# Ethernet_Shield_v2_0.net
KiCad netlist of a schematic drawn in EAGLE
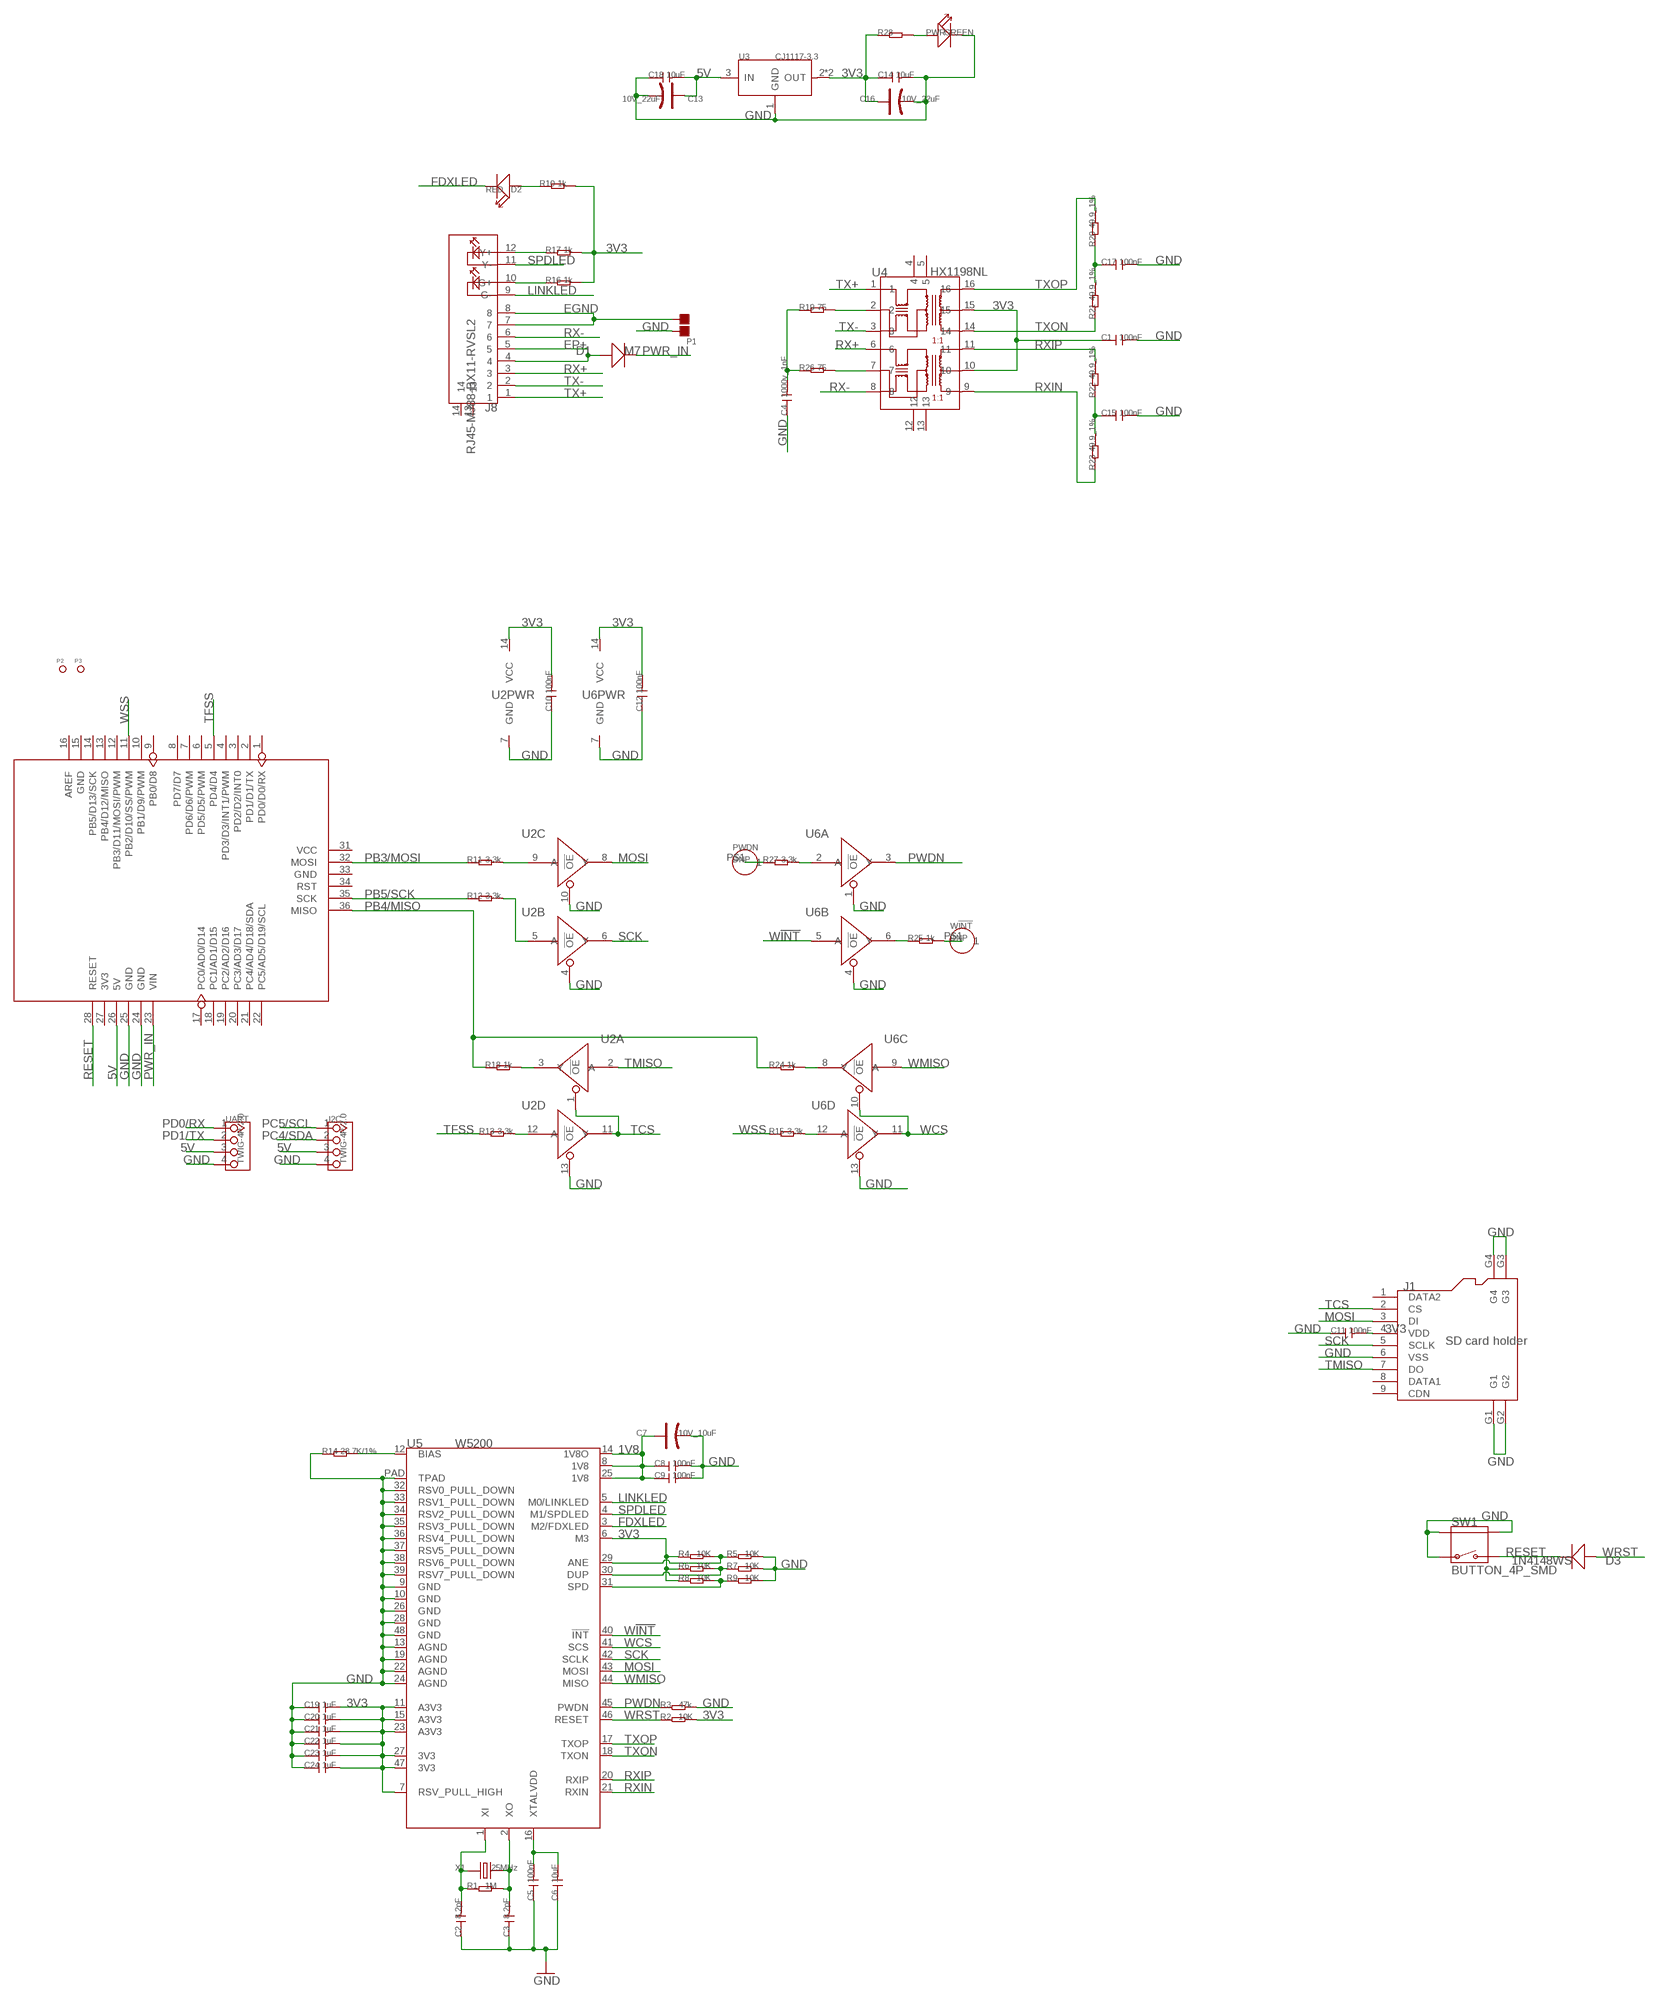
[diagram p0: schematic, sheet 1]

(export (version "E")
  (design (tool "Eeschema 10.0.6"))
  (components
    (comp (ref "C1")
      (value "100nF")
      (footprint "eagle-import:C0603")
      (libsource (lib "eagle-import") (part "C-0603"))
    )
    (comp (ref "C2")
      (value "8.2pF")
      (footprint "eagle-import:C0603")
      (libsource (lib "eagle-import") (part "C-0603"))
    )
    (comp (ref "C3")
      (value "8.2pF")
      (footprint "eagle-import:C0603")
      (libsource (lib "eagle-import") (part "C-0603"))
    )
    (comp (ref "C4")
      (value "1000v_1nF")
      (footprint "eagle-import:C1206")
      (libsource (lib "eagle-import") (part "C-1206"))
    )
    (comp (ref "C5")
      (value "100nF")
      (footprint "eagle-import:C0603")
      (libsource (lib "eagle-import") (part "C-0603"))
    )
    (comp (ref "C6")
      (value "10uF")
      (footprint "eagle-import:C0805")
      (libsource (lib "eagle-import") (part "C-0805"))
    )
    (comp (ref "C7")
      (value "10V_10uF")
      (footprint "eagle-import:AVX-A")
      (libsource (lib "eagle-import") (part "CAP-AVX-A"))
    )
    (comp (ref "C8")
      (value "100nF")
      (footprint "eagle-import:C0603")
      (libsource (lib "eagle-import") (part "C-0603"))
    )
    (comp (ref "C9")
      (value "100nF")
      (footprint "eagle-import:C0603")
      (libsource (lib "eagle-import") (part "C-0603"))
    )
    (comp (ref "C10")
      (value "100nF")
      (footprint "eagle-import:C0603")
      (libsource (lib "eagle-import") (part "C-0603"))
    )
    (comp (ref "C11")
      (value "100nF")
      (footprint "eagle-import:C0603")
      (libsource (lib "eagle-import") (part "C-0603"))
    )
    (comp (ref "C12")
      (value "100nF")
      (footprint "eagle-import:C0603")
      (libsource (lib "eagle-import") (part "C-0603"))
    )
    (comp (ref "C13")
      (value "10V_22uF")
      (footprint "eagle-import:AVX-B")
      (libsource (lib "eagle-import") (part "CAP-AVX-B"))
    )
    (comp (ref "C14")
      (value "10uF")
      (footprint "eagle-import:C0805")
      (libsource (lib "eagle-import") (part "C-0805"))
    )
    (comp (ref "C15")
      (value "100nF")
      (footprint "eagle-import:C0603")
      (libsource (lib "eagle-import") (part "C-0603"))
    )
    (comp (ref "C16")
      (value "10V_22uF")
      (footprint "eagle-import:AVX-B")
      (libsource (lib "eagle-import") (part "CAP-AVX-B"))
    )
    (comp (ref "C17")
      (value "100nF")
      (footprint "eagle-import:C0603")
      (libsource (lib "eagle-import") (part "C-0603"))
    )
    (comp (ref "C18")
      (value "10uF")
      (footprint "eagle-import:C0805")
      (libsource (lib "eagle-import") (part "C-0805"))
    )
    (comp (ref "C19")
      (value "1uF")
      (footprint "eagle-import:C0805")
      (libsource (lib "eagle-import") (part "C-0805"))
    )
    (comp (ref "C20")
      (value "1uF")
      (footprint "eagle-import:C0805")
      (libsource (lib "eagle-import") (part "C-0805"))
    )
    (comp (ref "C21")
      (value "1uF")
      (footprint "eagle-import:C0805")
      (libsource (lib "eagle-import") (part "C-0805"))
    )
    (comp (ref "C22")
      (value "1uF")
      (footprint "eagle-import:C0805")
      (libsource (lib "eagle-import") (part "C-0805"))
    )
    (comp (ref "C23")
      (value "1uF")
      (footprint "eagle-import:C0805")
      (libsource (lib "eagle-import") (part "C-0805"))
    )
    (comp (ref "C24")
      (value "1uF")
      (footprint "eagle-import:C0805")
      (libsource (lib "eagle-import") (part "C-0805"))
    )
    (comp (ref "D1")
      (value "M7")
      (footprint "eagle-import:D2010")
      (libsource (lib "eagle-import") (part "D'SMA'"))
    )
    (comp (ref "D2")
      (value "RED")
      (footprint "eagle-import:LED-0603")
      (libsource (lib "eagle-import") (part "LED'0603'"))
    )
    (comp (ref "D3")
      (value "1N4148WS")
      (footprint "eagle-import:SOD323")
      (libsource (lib "eagle-import") (part "D'0805'"))
    )
    (comp (ref "I2C")
      (value "TWIG-4P-2.0")
      (footprint "eagle-import:4P-2.0")
      (libsource (lib "eagle-import") (part "TWIG-4P-2.0-2.0"))
    )
    (comp (ref "J1")
      (value "SD card holder")
      (footprint "eagle-import:9P-SMD-W_-RING")
      (libsource (lib "eagle-import") (part "HOLDER-MICROSD-9P"))
    )
    (comp (ref "J8")
      (value "RJ45-MJ88-BX11-RVSL2")
      (footprint "eagle-import:RJ45-MJ88-BX11-RVSL2")
      (libsource (lib "eagle-import") (part "RJ45-MJ88-BX11-RVSL2"))
    )
    (comp (ref "P1")
      (value "DNP")
      (footprint "eagle-import:2P-SMD-1.78X1.27")
      (libsource (lib "eagle-import") (part "PAD-JUMPER-2P"))
    )
    (comp (ref "P2")
      (value "PAD-MARK")
      (footprint "eagle-import:ROUND-MARK-1.0")
      (fields (field (name "PARTNO") "DNP"))
      (libsource (lib "eagle-import") (part "PAD-MARK"))
    )
    (comp (ref "P3")
      (value "PAD-MARK")
      (footprint "eagle-import:ROUND-MARK-1.0")
      (fields (field (name "PARTNO") "DNP"))
      (libsource (lib "eagle-import") (part "PAD-MARK"))
    )
    (comp (ref "PWDN")
      (value "DNP")
      (footprint "eagle-import:1P-65_35MIL")
      (libsource (lib "eagle-import") (part "HEADER-1P-35"))
    )
    (comp (ref "PWR")
      (value "GREEN")
      (footprint "eagle-import:LED-0603")
      (libsource (lib "eagle-import") (part "LED'0603'"))
    )
    (comp (ref "R1")
      (value "1M")
      (footprint "eagle-import:R0603")
      (libsource (lib "eagle-import") (part "R-0603"))
    )
    (comp (ref "R2")
      (value "10K")
      (footprint "eagle-import:R0603")
      (libsource (lib "eagle-import") (part "R-0603"))
    )
    (comp (ref "R3")
      (value "47k")
      (footprint "eagle-import:R0603")
      (libsource (lib "eagle-import") (part "R-0603"))
    )
    (comp (ref "R4")
      (value "10K")
      (footprint "eagle-import:R0603")
      (libsource (lib "eagle-import") (part "R-0603"))
    )
    (comp (ref "R5")
      (value "10K")
      (footprint "eagle-import:R0603")
      (libsource (lib "eagle-import") (part "R-0603"))
    )
    (comp (ref "R6")
      (value "10K")
      (footprint "eagle-import:R0603")
      (libsource (lib "eagle-import") (part "R-0603"))
    )
    (comp (ref "R7")
      (value "10K")
      (footprint "eagle-import:R0603")
      (libsource (lib "eagle-import") (part "R-0603"))
    )
    (comp (ref "R8")
      (value "10K")
      (footprint "eagle-import:R0603")
      (libsource (lib "eagle-import") (part "R-0603"))
    )
    (comp (ref "R9")
      (value "10K")
      (footprint "eagle-import:R0603")
      (libsource (lib "eagle-import") (part "R-0603"))
    )
    (comp (ref "R10")
      (value "1k")
      (footprint "eagle-import:R0603")
      (libsource (lib "eagle-import") (part "R-0603"))
    )
    (comp (ref "R11")
      (value "3.3k")
      (footprint "eagle-import:R0603")
      (libsource (lib "eagle-import") (part "R-0603"))
    )
    (comp (ref "R12")
      (value "3.3k")
      (footprint "eagle-import:R0603")
      (libsource (lib "eagle-import") (part "R-0603"))
    )
    (comp (ref "R13")
      (value "3.3k")
      (footprint "eagle-import:R0603")
      (libsource (lib "eagle-import") (part "R-0603"))
    )
    (comp (ref "R14")
      (value "28.7K/1%")
      (footprint "eagle-import:R0603")
      (libsource (lib "eagle-import") (part "R-0603"))
    )
    (comp (ref "R15")
      (value "3.3k")
      (footprint "eagle-import:R0603")
      (libsource (lib "eagle-import") (part "R-0603"))
    )
    (comp (ref "R16")
      (value "1k")
      (footprint "eagle-import:R0603")
      (libsource (lib "eagle-import") (part "R-0603"))
    )
    (comp (ref "R17")
      (value "1k")
      (footprint "eagle-import:R0603")
      (libsource (lib "eagle-import") (part "R-0603"))
    )
    (comp (ref "R18")
      (value "1k")
      (footprint "eagle-import:R0603")
      (libsource (lib "eagle-import") (part "R-0603"))
    )
    (comp (ref "R19")
      (value "75")
      (footprint "eagle-import:R0603")
      (libsource (lib "eagle-import") (part "R-0603"))
    )
    (comp (ref "R20")
      (value "49.9_1%")
      (footprint "eagle-import:R0603")
      (libsource (lib "eagle-import") (part "R-0603"))
    )
    (comp (ref "R21")
      (value "49.9_1%")
      (footprint "eagle-import:R0603")
      (libsource (lib "eagle-import") (part "R-0603"))
    )
    (comp (ref "R22")
      (value "49.9_1%")
      (footprint "eagle-import:R0603")
      (libsource (lib "eagle-import") (part "R-0603"))
    )
    (comp (ref "R23")
      (value "49.9_1%")
      (footprint "eagle-import:R0603")
      (libsource (lib "eagle-import") (part "R-0603"))
    )
    (comp (ref "R24")
      (value "1k")
      (footprint "eagle-import:R0603")
      (libsource (lib "eagle-import") (part "R-0603"))
    )
    (comp (ref "R25")
      (value "1k")
      (footprint "eagle-import:R0603")
      (libsource (lib "eagle-import") (part "R-0603"))
    )
    (comp (ref "R26")
      (value "75")
      (footprint "eagle-import:R0603")
      (libsource (lib "eagle-import") (part "R-0603"))
    )
    (comp (ref "R27")
      (value "3.3k")
      (footprint "eagle-import:R0603")
      (libsource (lib "eagle-import") (part "R-0603"))
    )
    (comp (ref "R28")
      (value "R-0603")
      (footprint "eagle-import:R0603")
      (libsource (lib "eagle-import") (part "R-0603"))
    )
    (comp (ref "SW1")
      (value "BUTTON_4P_SMD")
      (footprint "eagle-import:4P-SMD-7X3.5X3.5")
      (libsource (lib "eagle-import") (part "BUTTON_4P_SMD"))
    )
    (comp (ref "U1")
      (value "ARDUINO")
      (footprint "eagle-import:ARDUINO")
      (libsource (lib "eagle-import") (part "ARDUINO"))
    )
    (comp (ref "U2")
      (value "74VHC125PW")
      (footprint "eagle-import:TSSOP14")
      (libsource (lib "eagle-import") (part "74V125PWHC"))
    )
    (comp (ref "U3")
      (value "CJ1117-3.3")
      (footprint "eagle-import:SOT-223")
      (libsource (lib "eagle-import") (part "LD1117S"))
    )
    (comp (ref "U4")
      (value "HX1198NL")
      (footprint "eagle-import:SOIC16-9.53")
      (libsource (lib "eagle-import") (part "HX1198NL"))
    )
    (comp (ref "U5")
      (value "W5200")
      (footprint "eagle-import:QFN48")
      (libsource (lib "eagle-import") (part "W5200"))
    )
    (comp (ref "U6")
      (value "74VHC125PW")
      (footprint "eagle-import:TSSOP14")
      (libsource (lib "eagle-import") (part "74V125PWHC"))
    )
    (comp (ref "UART")
      (value "TWIG-4P-2.0")
      (footprint "eagle-import:4P-2.0")
      (libsource (lib "eagle-import") (part "TWIG-4P-2.0-2.0"))
    )
    (comp (ref "W!INT")
      (value "DNP")
      (footprint "eagle-import:1P-65_35MIL")
      (libsource (lib "eagle-import") (part "HEADER-1P-35"))
    )
    (comp (ref "X1")
      (value "25MHz")
      (footprint "eagle-import:2P-SMD-5X3.2")
      (libsource (lib "eagle-import") (part "CRYSTAL'5032'"))
    )
  )
  (nets
    (net (code "1") (name "/1V8") (class "Default")
      (node (ref "C7") (pin "+") (pinfunction "+_+") (pintype "passive"))
      (node (ref "C8") (pin "1") (pinfunction "1_1") (pintype "passive"))
      (node (ref "C9") (pin "1") (pinfunction "1_1") (pintype "passive"))
      (node (ref "U5") (pin "14") (pinfunction "1V8O_14") (pintype "bidirectional"))
      (node (ref "U5") (pin "25") (pinfunction "1V8_25") (pintype "bidirectional"))
      (node (ref "U5") (pin "8") (pinfunction "1V8_8") (pintype "bidirectional"))
    )
    (net (code "2") (name "/3V3") (class "Default")
      (node (ref "C1") (pin "1") (pinfunction "1_1") (pintype "passive"))
      (node (ref "C10") (pin "2") (pinfunction "2_2") (pintype "passive"))
      (node (ref "C11") (pin "2") (pinfunction "2_2") (pintype "passive"))
      (node (ref "C12") (pin "2") (pinfunction "2_2") (pintype "passive"))
      (node (ref "C14") (pin "1") (pinfunction "1_1") (pintype "passive"))
      (node (ref "C16") (pin "+") (pinfunction "+_+") (pintype "passive"))
      (node (ref "C19") (pin "2") (pinfunction "2_2") (pintype "passive"))
      (node (ref "C20") (pin "2") (pinfunction "2_2") (pintype "passive"))
      (node (ref "C21") (pin "2") (pinfunction "2_2") (pintype "passive"))
      (node (ref "C22") (pin "2") (pinfunction "2_2") (pintype "passive"))
      (node (ref "C23") (pin "2") (pinfunction "2_2") (pintype "passive"))
      (node (ref "C24") (pin "2") (pinfunction "2_2") (pintype "passive"))
      (node (ref "J1") (pin "4") (pinfunction "VDD_4") (pintype "bidirectional"))
      (node (ref "R10") (pin "2") (pinfunction "2_2") (pintype "passive"))
      (node (ref "R16") (pin "2") (pinfunction "2_2") (pintype "passive"))
      (node (ref "R17") (pin "2") (pinfunction "2_2") (pintype "passive"))
      (node (ref "R2") (pin "2") (pinfunction "2_2") (pintype "passive"))
      (node (ref "R28") (pin "1") (pinfunction "1_1") (pintype "passive"))
      (node (ref "R4") (pin "1") (pinfunction "1_1") (pintype "passive"))
      (node (ref "R6") (pin "1") (pinfunction "1_1") (pintype "passive"))
      (node (ref "R8") (pin "1") (pinfunction "1_1") (pintype "passive"))
      (node (ref "U2") (pin "14") (pinfunction "VCC_14") (pintype "power_in"))
      (node (ref "U3") (pin "2") (pinfunction "OUT_2") (pintype "bidirectional"))
      (node (ref "U3") (pin "TER") (pinfunction "OUT_TER") (pintype "bidirectional"))
      (node (ref "U4") (pin "10") (pinfunction "10_10") (pintype "bidirectional"))
      (node (ref "U4") (pin "15") (pinfunction "15_15") (pintype "bidirectional"))
      (node (ref "U5") (pin "11") (pinfunction "A3V3_11") (pintype "bidirectional"))
      (node (ref "U5") (pin "15") (pinfunction "A3V3_15") (pintype "bidirectional"))
      (node (ref "U5") (pin "23") (pinfunction "A3V3_23") (pintype "bidirectional"))
      (node (ref "U5") (pin "27") (pinfunction "3V3_27") (pintype "bidirectional"))
      (node (ref "U5") (pin "47") (pinfunction "3V3_47") (pintype "bidirectional"))
      (node (ref "U5") (pin "6") (pinfunction "M3_6") (pintype "bidirectional"))
      (node (ref "U5") (pin "7") (pinfunction "RSV_PULL_HIGH_7") (pintype "bidirectional"))
      (node (ref "U6") (pin "14") (pinfunction "VCC_14") (pintype "power_in"))
    )
    (net (code "3") (name "/5V") (class "Default")
      (node (ref "C13") (pin "+") (pinfunction "+_+") (pintype "passive"))
      (node (ref "C18") (pin "2") (pinfunction "2_2") (pintype "passive"))
      (node (ref "I2C") (pin "3") (pinfunction "3_3") (pintype "bidirectional"))
      (node (ref "U1") (pin "26") (pinfunction "5V_26") (pintype "bidirectional"))
      (node (ref "U3") (pin "3") (pinfunction "IN_3") (pintype "bidirectional"))
      (node (ref "UART") (pin "3") (pinfunction "3_3") (pintype "bidirectional"))
    )
    (net (code "4") (name "/EGND") (class "Default")
      (node (ref "J8") (pin "7") (pinfunction "7_7") (pintype "bidirectional"))
      (node (ref "J8") (pin "8") (pinfunction "8_8") (pintype "bidirectional"))
      (node (ref "P1") (pin "1") (pinfunction "1_1") (pintype "bidirectional"))
    )
    (net (code "5") (name "/EP+") (class "Default")
      (node (ref "D1") (pin "+") (pinfunction "+_+") (pintype "passive"))
      (node (ref "J8") (pin "4") (pinfunction "4_4") (pintype "bidirectional"))
      (node (ref "J8") (pin "5") (pinfunction "5_5") (pintype "bidirectional"))
    )
    (net (code "6") (name "/FDXLED") (class "Default")
      (node (ref "D2") (pin "-") (pinfunction "-_-") (pintype "passive"))
      (node (ref "U5") (pin "3") (pinfunction "M2/FDXLED_3") (pintype "bidirectional"))
    )
    (net (code "7") (name "/LINKLED") (class "Default")
      (node (ref "J8") (pin "9") (pinfunction "G-_9") (pintype "bidirectional"))
      (node (ref "U5") (pin "5") (pinfunction "M0/LINKLED_5") (pintype "bidirectional"))
    )
    (net (code "8") (name "/MOSI") (class "Default")
      (node (ref "J1") (pin "3") (pinfunction "DI_3") (pintype "bidirectional"))
      (node (ref "U2") (pin "8") (pinfunction "Y_8") (pintype "bidirectional"))
      (node (ref "U5") (pin "43") (pinfunction "MOSI_43") (pintype "bidirectional"))
    )
    (net (code "9") (name "/PB3{slash}MOSI") (class "Default")
      (node (ref "R11") (pin "1") (pinfunction "1_1") (pintype "passive"))
      (node (ref "U1") (pin "32") (pinfunction "MOSI_32") (pintype "bidirectional"))
    )
    (net (code "10") (name "/PB4{slash}MISO") (class "Default")
      (node (ref "R18") (pin "1") (pinfunction "1_1") (pintype "passive"))
      (node (ref "R24") (pin "1") (pinfunction "1_1") (pintype "passive"))
      (node (ref "U1") (pin "36") (pinfunction "MISO_36") (pintype "bidirectional"))
    )
    (net (code "11") (name "/PB5{slash}SCK") (class "Default")
      (node (ref "R12") (pin "1") (pinfunction "1_1") (pintype "passive"))
      (node (ref "U1") (pin "35") (pinfunction "SCK_35") (pintype "bidirectional"))
    )
    (net (code "12") (name "/PC4{slash}SDA") (class "Default")
      (node (ref "I2C") (pin "2") (pinfunction "2_2") (pintype "bidirectional"))
    )
    (net (code "13") (name "/PC5{slash}SCL") (class "Default")
      (node (ref "I2C") (pin "1") (pinfunction "1_1") (pintype "bidirectional"))
    )
    (net (code "14") (name "/PD0{slash}RX") (class "Default")
      (node (ref "UART") (pin "1") (pinfunction "1_1") (pintype "bidirectional"))
    )
    (net (code "15") (name "/PD1{slash}TX") (class "Default")
      (node (ref "UART") (pin "2") (pinfunction "2_2") (pintype "bidirectional"))
    )
    (net (code "16") (name "/PWDN") (class "Default")
      (node (ref "R3") (pin "1") (pinfunction "1_1") (pintype "passive"))
      (node (ref "U5") (pin "45") (pinfunction "PWDN_45") (pintype "bidirectional"))
      (node (ref "U6") (pin "3") (pinfunction "Y_3") (pintype "bidirectional"))
    )
    (net (code "17") (name "/PWR_IN") (class "Default")
      (node (ref "D1") (pin "-") (pinfunction "-_-") (pintype "passive"))
      (node (ref "U1") (pin "23") (pinfunction "VIN_23") (pintype "bidirectional"))
    )
    (net (code "18") (name "/RESET") (class "Default")
      (node (ref "D3") (pin "-") (pinfunction "-_-") (pintype "passive"))
      (node (ref "SW1") (pin "2") (pinfunction "2_2") (pintype "bidirectional"))
      (node (ref "U1") (pin "28") (pinfunction "RESET_28") (pintype "bidirectional"))
    )
    (net (code "19") (name "/RX+") (class "Default")
      (node (ref "J8") (pin "3") (pinfunction "3_3") (pintype "bidirectional"))
      (node (ref "U4") (pin "6") (pinfunction "6_6") (pintype "bidirectional"))
    )
    (net (code "20") (name "/RX-") (class "Default")
      (node (ref "J8") (pin "6") (pinfunction "6_6") (pintype "bidirectional"))
      (node (ref "U4") (pin "8") (pinfunction "8_8") (pintype "bidirectional"))
    )
    (net (code "21") (name "/RXIN") (class "Default")
      (node (ref "R23") (pin "1") (pinfunction "1_1") (pintype "passive"))
      (node (ref "U4") (pin "9") (pinfunction "9_9") (pintype "bidirectional"))
      (node (ref "U5") (pin "21") (pinfunction "RXIN_21") (pintype "bidirectional"))
    )
    (net (code "22") (name "/RXIP") (class "Default")
      (node (ref "R22") (pin "2") (pinfunction "2_2") (pintype "passive"))
      (node (ref "U4") (pin "11") (pinfunction "11_11") (pintype "bidirectional"))
      (node (ref "U5") (pin "20") (pinfunction "RXIP_20") (pintype "bidirectional"))
    )
    (net (code "23") (name "/SCK") (class "Default")
      (node (ref "J1") (pin "5") (pinfunction "SCLK_5") (pintype "bidirectional"))
      (node (ref "U2") (pin "6") (pinfunction "Y_6") (pintype "bidirectional"))
      (node (ref "U5") (pin "42") (pinfunction "SCLK_42") (pintype "bidirectional"))
    )
    (net (code "24") (name "/SPDLED") (class "Default")
      (node (ref "J8") (pin "11") (pinfunction "Y-_11") (pintype "bidirectional"))
      (node (ref "U5") (pin "4") (pinfunction "M1/SPDLED_4") (pintype "bidirectional"))
    )
    (net (code "25") (name "/TCS") (class "Default")
      (node (ref "J1") (pin "2") (pinfunction "CS_2") (pintype "bidirectional"))
      (node (ref "U2") (pin "1") (pinfunction "~{OE}_1") (pintype "bidirectional"))
      (node (ref "U2") (pin "11") (pinfunction "Y_11") (pintype "bidirectional"))
    )
    (net (code "26") (name "/TFSS") (class "Default")
      (node (ref "R13") (pin "1") (pinfunction "1_1") (pintype "passive"))
      (node (ref "U1") (pin "5") (pinfunction "PD4/D4_5") (pintype "bidirectional"))
    )
    (net (code "27") (name "/TMISO") (class "Default")
      (node (ref "J1") (pin "7") (pinfunction "DO_7") (pintype "bidirectional"))
      (node (ref "U2") (pin "2") (pinfunction "A_2") (pintype "bidirectional"))
    )
    (net (code "28") (name "/TX+") (class "Default")
      (node (ref "J8") (pin "1") (pinfunction "1_1") (pintype "bidirectional"))
      (node (ref "U4") (pin "1") (pinfunction "1_1") (pintype "bidirectional"))
    )
    (net (code "29") (name "/TX-") (class "Default")
      (node (ref "J8") (pin "2") (pinfunction "2_2") (pintype "bidirectional"))
      (node (ref "U4") (pin "3") (pinfunction "3_3") (pintype "bidirectional"))
    )
    (net (code "30") (name "/TXON") (class "Default")
      (node (ref "R21") (pin "1") (pinfunction "1_1") (pintype "passive"))
      (node (ref "U4") (pin "14") (pinfunction "14_14") (pintype "bidirectional"))
      (node (ref "U5") (pin "18") (pinfunction "TXON_18") (pintype "bidirectional"))
    )
    (net (code "31") (name "/TXOP") (class "Default")
      (node (ref "R20") (pin "2") (pinfunction "2_2") (pintype "passive"))
      (node (ref "U4") (pin "16") (pinfunction "16_16") (pintype "bidirectional"))
      (node (ref "U5") (pin "17") (pinfunction "TXOP_17") (pintype "bidirectional"))
    )
    (net (code "32") (name "/WCS") (class "Default")
      (node (ref "U5") (pin "41") (pinfunction "SCS_41") (pintype "bidirectional"))
      (node (ref "U6") (pin "10") (pinfunction "~{OE}_10") (pintype "bidirectional"))
      (node (ref "U6") (pin "11") (pinfunction "Y_11") (pintype "bidirectional"))
    )
    (net (code "33") (name "/WMISO") (class "Default")
      (node (ref "U5") (pin "44") (pinfunction "MISO_44") (pintype "bidirectional"))
      (node (ref "U6") (pin "9") (pinfunction "A_9") (pintype "bidirectional"))
    )
    (net (code "34") (name "/WRST") (class "Default")
      (node (ref "D3") (pin "+") (pinfunction "+_+") (pintype "passive"))
      (node (ref "R2") (pin "1") (pinfunction "1_1") (pintype "passive"))
      (node (ref "U5") (pin "46") (pinfunction "RESET_46") (pintype "bidirectional"))
    )
    (net (code "35") (name "/WSS") (class "Default")
      (node (ref "R15") (pin "1") (pinfunction "1_1") (pintype "passive"))
      (node (ref "U1") (pin "11") (pinfunction "PB2/D10/SS/PWM_11") (pintype "bidirectional"))
    )
    (net (code "36") (name "/W~{INT}") (class "Default")
      (node (ref "U5") (pin "40") (pinfunction "~{INT}_40") (pintype "bidirectional"))
      (node (ref "U6") (pin "5") (pinfunction "A_5") (pintype "bidirectional"))
    )
    (net (code "37") (name "GND") (class "Default")
      (node (ref "C1") (pin "2") (pinfunction "2_2") (pintype "passive"))
      (node (ref "C10") (pin "1") (pinfunction "1_1") (pintype "passive"))
      (node (ref "C11") (pin "1") (pinfunction "1_1") (pintype "passive"))
      (node (ref "C12") (pin "1") (pinfunction "1_1") (pintype "passive"))
      (node (ref "C13") (pin "-") (pinfunction "-_-") (pintype "passive"))
      (node (ref "C14") (pin "2") (pinfunction "2_2") (pintype "passive"))
      (node (ref "C15") (pin "2") (pinfunction "2_2") (pintype "passive"))
      (node (ref "C16") (pin "-") (pinfunction "-_-") (pintype "passive"))
      (node (ref "C17") (pin "2") (pinfunction "2_2") (pintype "passive"))
      (node (ref "C18") (pin "1") (pinfunction "1_1") (pintype "passive"))
      (node (ref "C19") (pin "1") (pinfunction "1_1") (pintype "passive"))
      (node (ref "C2") (pin "1") (pinfunction "1_1") (pintype "passive"))
      (node (ref "C20") (pin "1") (pinfunction "1_1") (pintype "passive"))
      (node (ref "C21") (pin "1") (pinfunction "1_1") (pintype "passive"))
      (node (ref "C22") (pin "1") (pinfunction "1_1") (pintype "passive"))
      (node (ref "C23") (pin "1") (pinfunction "1_1") (pintype "passive"))
      (node (ref "C24") (pin "1") (pinfunction "1_1") (pintype "passive"))
      (node (ref "C3") (pin "1") (pinfunction "1_1") (pintype "passive"))
      (node (ref "C4") (pin "1") (pinfunction "1_1") (pintype "passive"))
      (node (ref "C5") (pin "1") (pinfunction "1_1") (pintype "passive"))
      (node (ref "C6") (pin "1") (pinfunction "1_1") (pintype "passive"))
      (node (ref "C7") (pin "-") (pinfunction "-_-") (pintype "passive"))
      (node (ref "C8") (pin "2") (pinfunction "2_2") (pintype "passive"))
      (node (ref "C9") (pin "2") (pinfunction "2_2") (pintype "passive"))
      (node (ref "I2C") (pin "4") (pinfunction "4_4") (pintype "bidirectional"))
      (node (ref "J1") (pin "6") (pinfunction "VSS_6") (pintype "bidirectional"))
      (node (ref "J1") (pin "G1") (pinfunction "G1_G1") (pintype "bidirectional"))
      (node (ref "J1") (pin "G2") (pinfunction "G2_G2") (pintype "bidirectional"))
      (node (ref "J1") (pin "G3") (pinfunction "G3_G3") (pintype "bidirectional"))
      (node (ref "J1") (pin "G4") (pinfunction "G4_G4") (pintype "bidirectional"))
      (node (ref "P1") (pin "2") (pinfunction "2_2") (pintype "bidirectional"))
      (node (ref "PWR") (pin "-") (pinfunction "-_-") (pintype "passive"))
      (node (ref "R14") (pin "1") (pinfunction "1_1") (pintype "passive"))
      (node (ref "R3") (pin "2") (pinfunction "2_2") (pintype "passive"))
      (node (ref "R5") (pin "2") (pinfunction "2_2") (pintype "passive"))
      (node (ref "R7") (pin "2") (pinfunction "2_2") (pintype "passive"))
      (node (ref "R9") (pin "2") (pinfunction "2_2") (pintype "passive"))
      (node (ref "SW1") (pin "1") (pinfunction "1_1") (pintype "bidirectional"))
      (node (ref "SW1") (pin "S1") (pinfunction "S1_S1") (pintype "bidirectional"))
      (node (ref "SW1") (pin "S2") (pinfunction "S2_S2") (pintype "bidirectional"))
      (node (ref "U1") (pin "24") (pinfunction "GND_24") (pintype "bidirectional"))
      (node (ref "U1") (pin "25") (pinfunction "GND_25") (pintype "bidirectional"))
      (node (ref "U2") (pin "10") (pinfunction "~{OE}_10") (pintype "bidirectional"))
      (node (ref "U2") (pin "13") (pinfunction "~{OE}_13") (pintype "bidirectional"))
      (node (ref "U2") (pin "4") (pinfunction "~{OE}_4") (pintype "bidirectional"))
      (node (ref "U2") (pin "7") (pinfunction "GND_7") (pintype "power_in"))
      (node (ref "U3") (pin "1") (pinfunction "GND_1") (pintype "bidirectional"))
      (node (ref "U5") (pin "10") (pinfunction "GND_10") (pintype "bidirectional"))
      (node (ref "U5") (pin "13") (pinfunction "AGND_13") (pintype "bidirectional"))
      (node (ref "U5") (pin "19") (pinfunction "AGND_19") (pintype "bidirectional"))
      (node (ref "U5") (pin "22") (pinfunction "AGND_22") (pintype "bidirectional"))
      (node (ref "U5") (pin "24") (pinfunction "AGND_24") (pintype "bidirectional"))
      (node (ref "U5") (pin "26") (pinfunction "GND_26") (pintype "bidirectional"))
      (node (ref "U5") (pin "28") (pinfunction "GND_28") (pintype "bidirectional"))
      (node (ref "U5") (pin "32") (pinfunction "RSV0_PULL_DOWN_32") (pintype "bidirectional"))
      (node (ref "U5") (pin "33") (pinfunction "RSV1_PULL_DOWN_33") (pintype "bidirectional"))
      (node (ref "U5") (pin "34") (pinfunction "RSV2_PULL_DOWN_34") (pintype "bidirectional"))
      (node (ref "U5") (pin "35") (pinfunction "RSV3_PULL_DOWN_35") (pintype "bidirectional"))
      (node (ref "U5") (pin "36") (pinfunction "RSV4_PULL_DOWN_36") (pintype "bidirectional"))
      (node (ref "U5") (pin "37") (pinfunction "RSV5_PULL_DOWN_37") (pintype "bidirectional"))
      (node (ref "U5") (pin "38") (pinfunction "RSV6_PULL_DOWN_38") (pintype "bidirectional"))
      (node (ref "U5") (pin "39") (pinfunction "RSV7_PULL_DOWN_39") (pintype "bidirectional"))
      (node (ref "U5") (pin "48") (pinfunction "GND_48") (pintype "bidirectional"))
      (node (ref "U5") (pin "9") (pinfunction "GND_9") (pintype "bidirectional"))
      (node (ref "U5") (pin "PAD") (pinfunction "TPAD_PAD") (pintype "bidirectional"))
      (node (ref "U6") (pin "1") (pinfunction "~{OE}_1") (pintype "bidirectional"))
      (node (ref "U6") (pin "13") (pinfunction "~{OE}_13") (pintype "bidirectional"))
      (node (ref "U6") (pin "4") (pinfunction "~{OE}_4") (pintype "bidirectional"))
      (node (ref "U6") (pin "7") (pinfunction "GND_7") (pintype "power_in"))
      (node (ref "UART") (pin "4") (pinfunction "4_4") (pintype "bidirectional"))
    )
    (net (code "38") (name "Net-(C4-Pad2)") (class "Default")
      (node (ref "C4") (pin "2") (pinfunction "2_2") (pintype "passive"))
      (node (ref "R19") (pin "1") (pinfunction "1_1") (pintype "passive"))
      (node (ref "R26") (pin "1") (pinfunction "1_1") (pintype "passive"))
    )
    (net (code "39") (name "Net-(C15-Pad1)") (class "Default")
      (node (ref "C15") (pin "1") (pinfunction "1_1") (pintype "passive"))
      (node (ref "R22") (pin "1") (pinfunction "1_1") (pintype "passive"))
      (node (ref "R23") (pin "2") (pinfunction "2_2") (pintype "passive"))
    )
    (net (code "40") (name "Net-(C17-Pad1)") (class "Default")
      (node (ref "C17") (pin "1") (pinfunction "1_1") (pintype "passive"))
      (node (ref "R20") (pin "1") (pinfunction "1_1") (pintype "passive"))
      (node (ref "R21") (pin "2") (pinfunction "2_2") (pintype "passive"))
    )
    (net (code "41") (name "Net-(D2-Pad+)") (class "Default")
      (node (ref "D2") (pin "+") (pinfunction "+_+") (pintype "passive"))
      (node (ref "R10") (pin "1") (pinfunction "1_1") (pintype "passive"))
    )
    (net (code "42") (name "Net-(J8-G+)") (class "Default")
      (node (ref "J8") (pin "10") (pinfunction "G+_10") (pintype "bidirectional"))
      (node (ref "R16") (pin "1") (pinfunction "1_1") (pintype "passive"))
    )
    (net (code "43") (name "Net-(J8-Y+)") (class "Default")
      (node (ref "J8") (pin "12") (pinfunction "Y+_12") (pintype "bidirectional"))
      (node (ref "R17") (pin "1") (pinfunction "1_1") (pintype "passive"))
    )
    (net (code "44") (name "Net-(PWDN-1)") (class "Default")
      (node (ref "PWDN") (pin "P$1") (pinfunction "1_P$1") (pintype "bidirectional"))
      (node (ref "R27") (pin "1") (pinfunction "1_1") (pintype "passive"))
    )
    (net (code "45") (name "Net-(PWR-Pad+)") (class "Default")
      (node (ref "PWR") (pin "+") (pinfunction "+_+") (pintype "passive"))
      (node (ref "R28") (pin "2") (pinfunction "2_2") (pintype "passive"))
    )
    (net (code "46") (name "Net-(R19-Pad2)") (class "Default")
      (node (ref "R19") (pin "2") (pinfunction "2_2") (pintype "passive"))
      (node (ref "U4") (pin "2") (pinfunction "2_2") (pintype "bidirectional"))
    )
    (net (code "47") (name "Net-(R26-Pad2)") (class "Default")
      (node (ref "R26") (pin "2") (pinfunction "2_2") (pintype "passive"))
      (node (ref "U4") (pin "7") (pinfunction "7_7") (pintype "bidirectional"))
    )
    (net (code "48") (name "Net-(U2A-Y)") (class "Default")
      (node (ref "R18") (pin "2") (pinfunction "2_2") (pintype "passive"))
      (node (ref "U2") (pin "3") (pinfunction "Y_3") (pintype "bidirectional"))
    )
    (net (code "49") (name "Net-(U2B-A)") (class "Default")
      (node (ref "R12") (pin "2") (pinfunction "2_2") (pintype "passive"))
      (node (ref "U2") (pin "5") (pinfunction "A_5") (pintype "bidirectional"))
    )
    (net (code "50") (name "Net-(U2C-A)") (class "Default")
      (node (ref "R11") (pin "2") (pinfunction "2_2") (pintype "passive"))
      (node (ref "U2") (pin "9") (pinfunction "A_9") (pintype "bidirectional"))
    )
    (net (code "51") (name "Net-(U2D-A)") (class "Default")
      (node (ref "R13") (pin "2") (pinfunction "2_2") (pintype "passive"))
      (node (ref "U2") (pin "12") (pinfunction "A_12") (pintype "bidirectional"))
    )
    (net (code "52") (name "Net-(U5-ANE)") (class "Default")
      (node (ref "R4") (pin "2") (pinfunction "2_2") (pintype "passive"))
      (node (ref "R5") (pin "1") (pinfunction "1_1") (pintype "passive"))
      (node (ref "U5") (pin "29") (pinfunction "ANE_29") (pintype "bidirectional"))
    )
    (net (code "53") (name "Net-(U5-BIAS)") (class "Default")
      (node (ref "R14") (pin "2") (pinfunction "2_2") (pintype "passive"))
      (node (ref "U5") (pin "12") (pinfunction "BIAS_12") (pintype "bidirectional"))
    )
    (net (code "54") (name "Net-(U5-DUP)") (class "Default")
      (node (ref "R6") (pin "2") (pinfunction "2_2") (pintype "passive"))
      (node (ref "R7") (pin "1") (pinfunction "1_1") (pintype "passive"))
      (node (ref "U5") (pin "30") (pinfunction "DUP_30") (pintype "bidirectional"))
    )
    (net (code "55") (name "Net-(U5-SPD)") (class "Default")
      (node (ref "R8") (pin "2") (pinfunction "2_2") (pintype "passive"))
      (node (ref "R9") (pin "1") (pinfunction "1_1") (pintype "passive"))
      (node (ref "U5") (pin "31") (pinfunction "SPD_31") (pintype "bidirectional"))
    )
    (net (code "56") (name "Net-(U5-XI)") (class "Default")
      (node (ref "C2") (pin "2") (pinfunction "2_2") (pintype "passive"))
      (node (ref "R1") (pin "1") (pinfunction "1_1") (pintype "passive"))
      (node (ref "U5") (pin "1") (pinfunction "XI_1") (pintype "bidirectional"))
      (node (ref "X1") (pin "1") (pinfunction "1_1") (pintype "passive"))
    )
    (net (code "57") (name "Net-(U5-XO)") (class "Default")
      (node (ref "C3") (pin "2") (pinfunction "2_2") (pintype "passive"))
      (node (ref "R1") (pin "2") (pinfunction "2_2") (pintype "passive"))
      (node (ref "U5") (pin "2") (pinfunction "XO_2") (pintype "bidirectional"))
      (node (ref "X1") (pin "2") (pinfunction "2_2") (pintype "passive"))
    )
    (net (code "58") (name "Net-(U5-XTALVDD)") (class "Default")
      (node (ref "C5") (pin "2") (pinfunction "2_2") (pintype "passive"))
      (node (ref "C6") (pin "2") (pinfunction "2_2") (pintype "passive"))
      (node (ref "U5") (pin "16") (pinfunction "XTALVDD_16") (pintype "bidirectional"))
    )
    (net (code "59") (name "Net-(U6A-A)") (class "Default")
      (node (ref "R27") (pin "2") (pinfunction "2_2") (pintype "passive"))
      (node (ref "U6") (pin "2") (pinfunction "A_2") (pintype "bidirectional"))
    )
    (net (code "60") (name "Net-(U6B-Y)") (class "Default")
      (node (ref "R25") (pin "1") (pinfunction "1_1") (pintype "passive"))
      (node (ref "U6") (pin "6") (pinfunction "Y_6") (pintype "bidirectional"))
    )
    (net (code "61") (name "Net-(U6C-Y)") (class "Default")
      (node (ref "R24") (pin "2") (pinfunction "2_2") (pintype "passive"))
      (node (ref "U6") (pin "8") (pinfunction "Y_8") (pintype "bidirectional"))
    )
    (net (code "62") (name "Net-(U6D-A)") (class "Default")
      (node (ref "R15") (pin "2") (pinfunction "2_2") (pintype "passive"))
      (node (ref "U6") (pin "12") (pinfunction "A_12") (pintype "bidirectional"))
    )
    (net (code "63") (name "Net-(W!INT-1)") (class "Default")
      (node (ref "R25") (pin "2") (pinfunction "2_2") (pintype "passive"))
      (node (ref "W!INT") (pin "P$1") (pinfunction "1_P$1") (pintype "bidirectional"))
    )
    (net (code "64") (name "unconnected-(J1-CDN-Pad9)") (class "Default")
      (node (ref "J1") (pin "9") (pinfunction "CDN_9") (pintype "bidirectional"))
    )
    (net (code "65") (name "unconnected-(J1-DATA1-Pad8)") (class "Default")
      (node (ref "J1") (pin "8") (pinfunction "DATA1_8") (pintype "bidirectional"))
    )
    (net (code "66") (name "unconnected-(J1-DATA2-Pad1)") (class "Default")
      (node (ref "J1") (pin "1") (pinfunction "DATA2_1") (pintype "bidirectional"))
    )
    (net (code "67") (name "unconnected-(J8-Pad13)") (class "Default")
      (node (ref "J8") (pin "13") (pinfunction "13_13") (pintype "bidirectional"))
    )
    (net (code "68") (name "unconnected-(J8-Pad14)") (class "Default")
      (node (ref "J8") (pin "14") (pinfunction "14_14") (pintype "bidirectional"))
    )
    (net (code "69") (name "unconnected-(U1-3V3-Pad27)") (class "Default")
      (node (ref "U1") (pin "27") (pinfunction "3V3_27") (pintype "bidirectional"))
    )
    (net (code "70") (name "unconnected-(U1-AREF-Pad16)") (class "Default")
      (node (ref "U1") (pin "16") (pinfunction "AREF_16") (pintype "bidirectional"))
    )
    (net (code "71") (name "unconnected-(U1-GND-Pad15)") (class "Default")
      (node (ref "U1") (pin "15") (pinfunction "GND_15") (pintype "bidirectional"))
    )
    (net (code "72") (name "unconnected-(U1-GND-Pad33)") (class "Default")
      (node (ref "U1") (pin "33") (pinfunction "GND_33") (pintype "bidirectional"))
    )
    (net (code "73") (name "unconnected-(U1-PB0{slash}D8-Pad9)") (class "Default")
      (node (ref "U1") (pin "9") (pinfunction "PB0/D8_9") (pintype "bidirectional"))
    )
    (net (code "74") (name "unconnected-(U1-PB1{slash}D9{slash}PWM-Pad10)") (class "Default")
      (node (ref "U1") (pin "10") (pinfunction "PB1/D9/PWM_10") (pintype "bidirectional"))
    )
    (net (code "75") (name "unconnected-(U1-PB3{slash}D11{slash}MOSI{slash}PWM-Pad12)") (class "Default")
      (node (ref "U1") (pin "12") (pinfunction "PB3/D11/MOSI/PWM_12") (pintype "bidirectional"))
    )
    (net (code "76") (name "unconnected-(U1-PB4{slash}D12{slash}MISO-Pad13)") (class "Default")
      (node (ref "U1") (pin "13") (pinfunction "PB4/D12/MISO_13") (pintype "bidirectional"))
    )
    (net (code "77") (name "unconnected-(U1-PB5{slash}D13{slash}SCK-Pad14)") (class "Default")
      (node (ref "U1") (pin "14") (pinfunction "PB5/D13/SCK_14") (pintype "bidirectional"))
    )
    (net (code "78") (name "unconnected-(U1-PC0{slash}AD0{slash}D14-Pad17)") (class "Default")
      (node (ref "U1") (pin "17") (pinfunction "PC0/AD0/D14_17") (pintype "bidirectional"))
    )
    (net (code "79") (name "unconnected-(U1-PC1{slash}AD1{slash}D15-Pad18)") (class "Default")
      (node (ref "U1") (pin "18") (pinfunction "PC1/AD1/D15_18") (pintype "bidirectional"))
    )
    (net (code "80") (name "unconnected-(U1-PC2{slash}AD2{slash}D16-Pad19)") (class "Default")
      (node (ref "U1") (pin "19") (pinfunction "PC2/AD2/D16_19") (pintype "bidirectional"))
    )
    (net (code "81") (name "unconnected-(U1-PC3{slash}AD3{slash}D17-Pad20)") (class "Default")
      (node (ref "U1") (pin "20") (pinfunction "PC3/AD3/D17_20") (pintype "bidirectional"))
    )
    (net (code "82") (name "unconnected-(U1-PC4{slash}AD4{slash}D18{slash}SDA-Pad21)") (class "Default")
      (node (ref "U1") (pin "21") (pinfunction "PC4/AD4/D18/SDA_21") (pintype "bidirectional"))
    )
    (net (code "83") (name "unconnected-(U1-PC5{slash}AD5{slash}D19{slash}SCL-Pad22)") (class "Default")
      (node (ref "U1") (pin "22") (pinfunction "PC5/AD5/D19/SCL_22") (pintype "bidirectional"))
    )
    (net (code "84") (name "unconnected-(U1-PD0{slash}D0{slash}RX-Pad1)") (class "Default")
      (node (ref "U1") (pin "1") (pinfunction "PD0/D0/RX_1") (pintype "bidirectional"))
    )
    (net (code "85") (name "unconnected-(U1-PD1{slash}D1{slash}TX-Pad2)") (class "Default")
      (node (ref "U1") (pin "2") (pinfunction "PD1/D1/TX_2") (pintype "bidirectional"))
    )
    (net (code "86") (name "unconnected-(U1-PD2{slash}D2{slash}INT0-Pad3)") (class "Default")
      (node (ref "U1") (pin "3") (pinfunction "PD2/D2/INT0_3") (pintype "bidirectional"))
    )
    (net (code "87") (name "unconnected-(U1-PD3{slash}D3{slash}INT1{slash}PWM-Pad4)") (class "Default")
      (node (ref "U1") (pin "4") (pinfunction "PD3/D3/INT1/PWM_4") (pintype "bidirectional"))
    )
    (net (code "88") (name "unconnected-(U1-PD5{slash}D5{slash}PWM-Pad6)") (class "Default")
      (node (ref "U1") (pin "6") (pinfunction "PD5/D5/PWM_6") (pintype "bidirectional"))
    )
    (net (code "89") (name "unconnected-(U1-PD6{slash}D6{slash}PWM-Pad7)") (class "Default")
      (node (ref "U1") (pin "7") (pinfunction "PD6/D6/PWM_7") (pintype "bidirectional"))
    )
    (net (code "90") (name "unconnected-(U1-PD7{slash}D7-Pad8)") (class "Default")
      (node (ref "U1") (pin "8") (pinfunction "PD7/D7_8") (pintype "bidirectional"))
    )
    (net (code "91") (name "unconnected-(U1-RST-Pad34)") (class "Default")
      (node (ref "U1") (pin "34") (pinfunction "RST_34") (pintype "bidirectional"))
    )
    (net (code "92") (name "unconnected-(U1-VCC-Pad31)") (class "Default")
      (node (ref "U1") (pin "31") (pinfunction "VCC_31") (pintype "bidirectional"))
    )
    (net (code "93") (name "unconnected-(U4-Pad4)") (class "Default")
      (node (ref "U4") (pin "4") (pinfunction "4_4") (pintype "bidirectional"))
    )
    (net (code "94") (name "unconnected-(U4-Pad5)") (class "Default")
      (node (ref "U4") (pin "5") (pinfunction "5_5") (pintype "bidirectional"))
    )
    (net (code "95") (name "unconnected-(U4-Pad12)") (class "Default")
      (node (ref "U4") (pin "12") (pinfunction "12_12") (pintype "bidirectional"))
    )
    (net (code "96") (name "unconnected-(U4-Pad13)") (class "Default")
      (node (ref "U4") (pin "13") (pinfunction "13_13") (pintype "bidirectional"))
    )
  )
)
